# RPi-I2C-LevelShifter.net
KiCad netlist of a schematic drawn in EAGLE
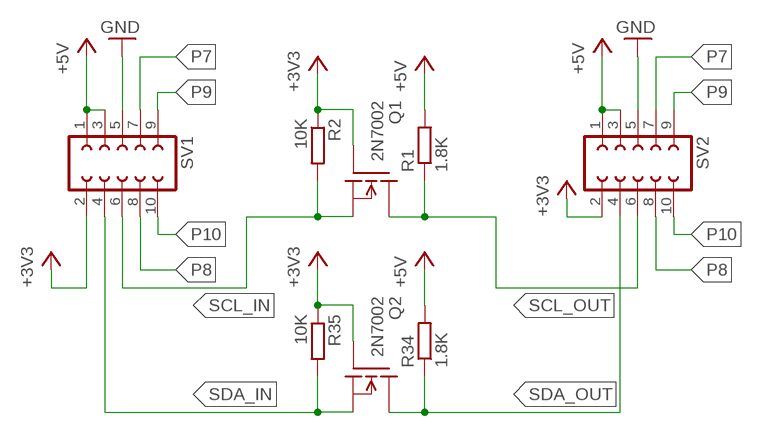
[diagram p0: schematic, sheet 1]

(export (version "E")
  (design (tool "Eeschema 10.0.6"))
  (components
    (comp (ref "Q1")
      (value "2N7002")
      (footprint "eagle-import:SOT23")
      (libsource (lib "eagle-import") (part "2N7002"))
    )
    (comp (ref "Q2")
      (value "2N7002")
      (footprint "eagle-import:SOT23")
      (libsource (lib "eagle-import") (part "2N7002"))
    )
    (comp (ref "R1")
      (value "1.8K")
      (footprint "eagle-import:R0805")
      (libsource (lib "eagle-import") (part "R-EU_R0805"))
    )
    (comp (ref "R2")
      (value "10K")
      (footprint "eagle-import:R0805")
      (libsource (lib "eagle-import") (part "R-EU_R0805"))
    )
    (comp (ref "R34")
      (value "1.8K")
      (footprint "eagle-import:R0805")
      (libsource (lib "eagle-import") (part "R-EU_R0805"))
    )
    (comp (ref "R35")
      (value "10K")
      (footprint "eagle-import:R0805")
      (libsource (lib "eagle-import") (part "R-EU_R0805"))
    )
    (comp (ref "SV1")
      (value "FE05-2")
      (footprint "eagle-import:FE05-2")
      (libsource (lib "eagle-import") (part "FE05-2"))
    )
    (comp (ref "SV2")
      (value "FE05-2")
      (footprint "eagle-import:FE05-2")
      (libsource (lib "eagle-import") (part "FE05-2"))
    )
  )
  (nets
    (net (code "1") (name "+3V3") (class "Default")
      (node (ref "Q1") (pin "1") (pinfunction "G_1") (pintype "passive"))
      (node (ref "Q2") (pin "1") (pinfunction "G_1") (pintype "passive"))
      (node (ref "R2") (pin "1") (pinfunction "1_1") (pintype "passive"))
      (node (ref "R35") (pin "1") (pinfunction "1_1") (pintype "passive"))
      (node (ref "SV1") (pin "2") (pinfunction "2_2") (pintype "passive"))
      (node (ref "SV2") (pin "2") (pinfunction "2_2") (pintype "passive"))
    )
    (net (code "2") (name "+5V") (class "Default")
      (node (ref "R1") (pin "2") (pinfunction "2_2") (pintype "passive"))
      (node (ref "R34") (pin "2") (pinfunction "2_2") (pintype "passive"))
      (node (ref "SV1") (pin "1") (pinfunction "1_1") (pintype "passive"))
      (node (ref "SV1") (pin "3") (pinfunction "3_3") (pintype "passive"))
      (node (ref "SV2") (pin "1") (pinfunction "1_1") (pintype "passive"))
      (node (ref "SV2") (pin "3") (pinfunction "3_3") (pintype "passive"))
    )
    (net (code "3") (name "GND") (class "Default")
      (node (ref "SV1") (pin "5") (pinfunction "5_5") (pintype "passive"))
      (node (ref "SV2") (pin "5") (pinfunction "5_5") (pintype "passive"))
    )
    (net (code "4") (name "P7") (class "Default")
      (node (ref "SV1") (pin "7") (pinfunction "7_7") (pintype "passive"))
      (node (ref "SV2") (pin "7") (pinfunction "7_7") (pintype "passive"))
    )
    (net (code "5") (name "P8") (class "Default")
      (node (ref "SV1") (pin "8") (pinfunction "8_8") (pintype "passive"))
      (node (ref "SV2") (pin "8") (pinfunction "8_8") (pintype "passive"))
    )
    (net (code "6") (name "P9") (class "Default")
      (node (ref "SV1") (pin "9") (pinfunction "9_9") (pintype "passive"))
      (node (ref "SV2") (pin "9") (pinfunction "9_9") (pintype "passive"))
    )
    (net (code "7") (name "P10") (class "Default")
      (node (ref "SV1") (pin "10") (pinfunction "10_10") (pintype "passive"))
      (node (ref "SV2") (pin "10") (pinfunction "10_10") (pintype "passive"))
    )
    (net (code "8") (name "SCL_IN") (class "Default")
      (node (ref "Q1") (pin "2") (pinfunction "S_2") (pintype "passive"))
      (node (ref "R2") (pin "2") (pinfunction "2_2") (pintype "passive"))
      (node (ref "SV1") (pin "6") (pinfunction "6_6") (pintype "passive"))
    )
    (net (code "9") (name "SCL_OUT") (class "Default")
      (node (ref "Q1") (pin "3") (pinfunction "D_3") (pintype "passive"))
      (node (ref "R1") (pin "1") (pinfunction "1_1") (pintype "passive"))
      (node (ref "SV2") (pin "6") (pinfunction "6_6") (pintype "passive"))
    )
    (net (code "10") (name "SDA_IN") (class "Default")
      (node (ref "Q2") (pin "2") (pinfunction "S_2") (pintype "passive"))
      (node (ref "R35") (pin "2") (pinfunction "2_2") (pintype "passive"))
      (node (ref "SV1") (pin "4") (pinfunction "4_4") (pintype "passive"))
    )
    (net (code "11") (name "SDA_OUT") (class "Default")
      (node (ref "Q2") (pin "3") (pinfunction "D_3") (pintype "passive"))
      (node (ref "R34") (pin "1") (pinfunction "1_1") (pintype "passive"))
      (node (ref "SV2") (pin "4") (pinfunction "4_4") (pintype "passive"))
    )
  )
)
